# lpf.net
KiCad netlist of a schematic drawn in EAGLE
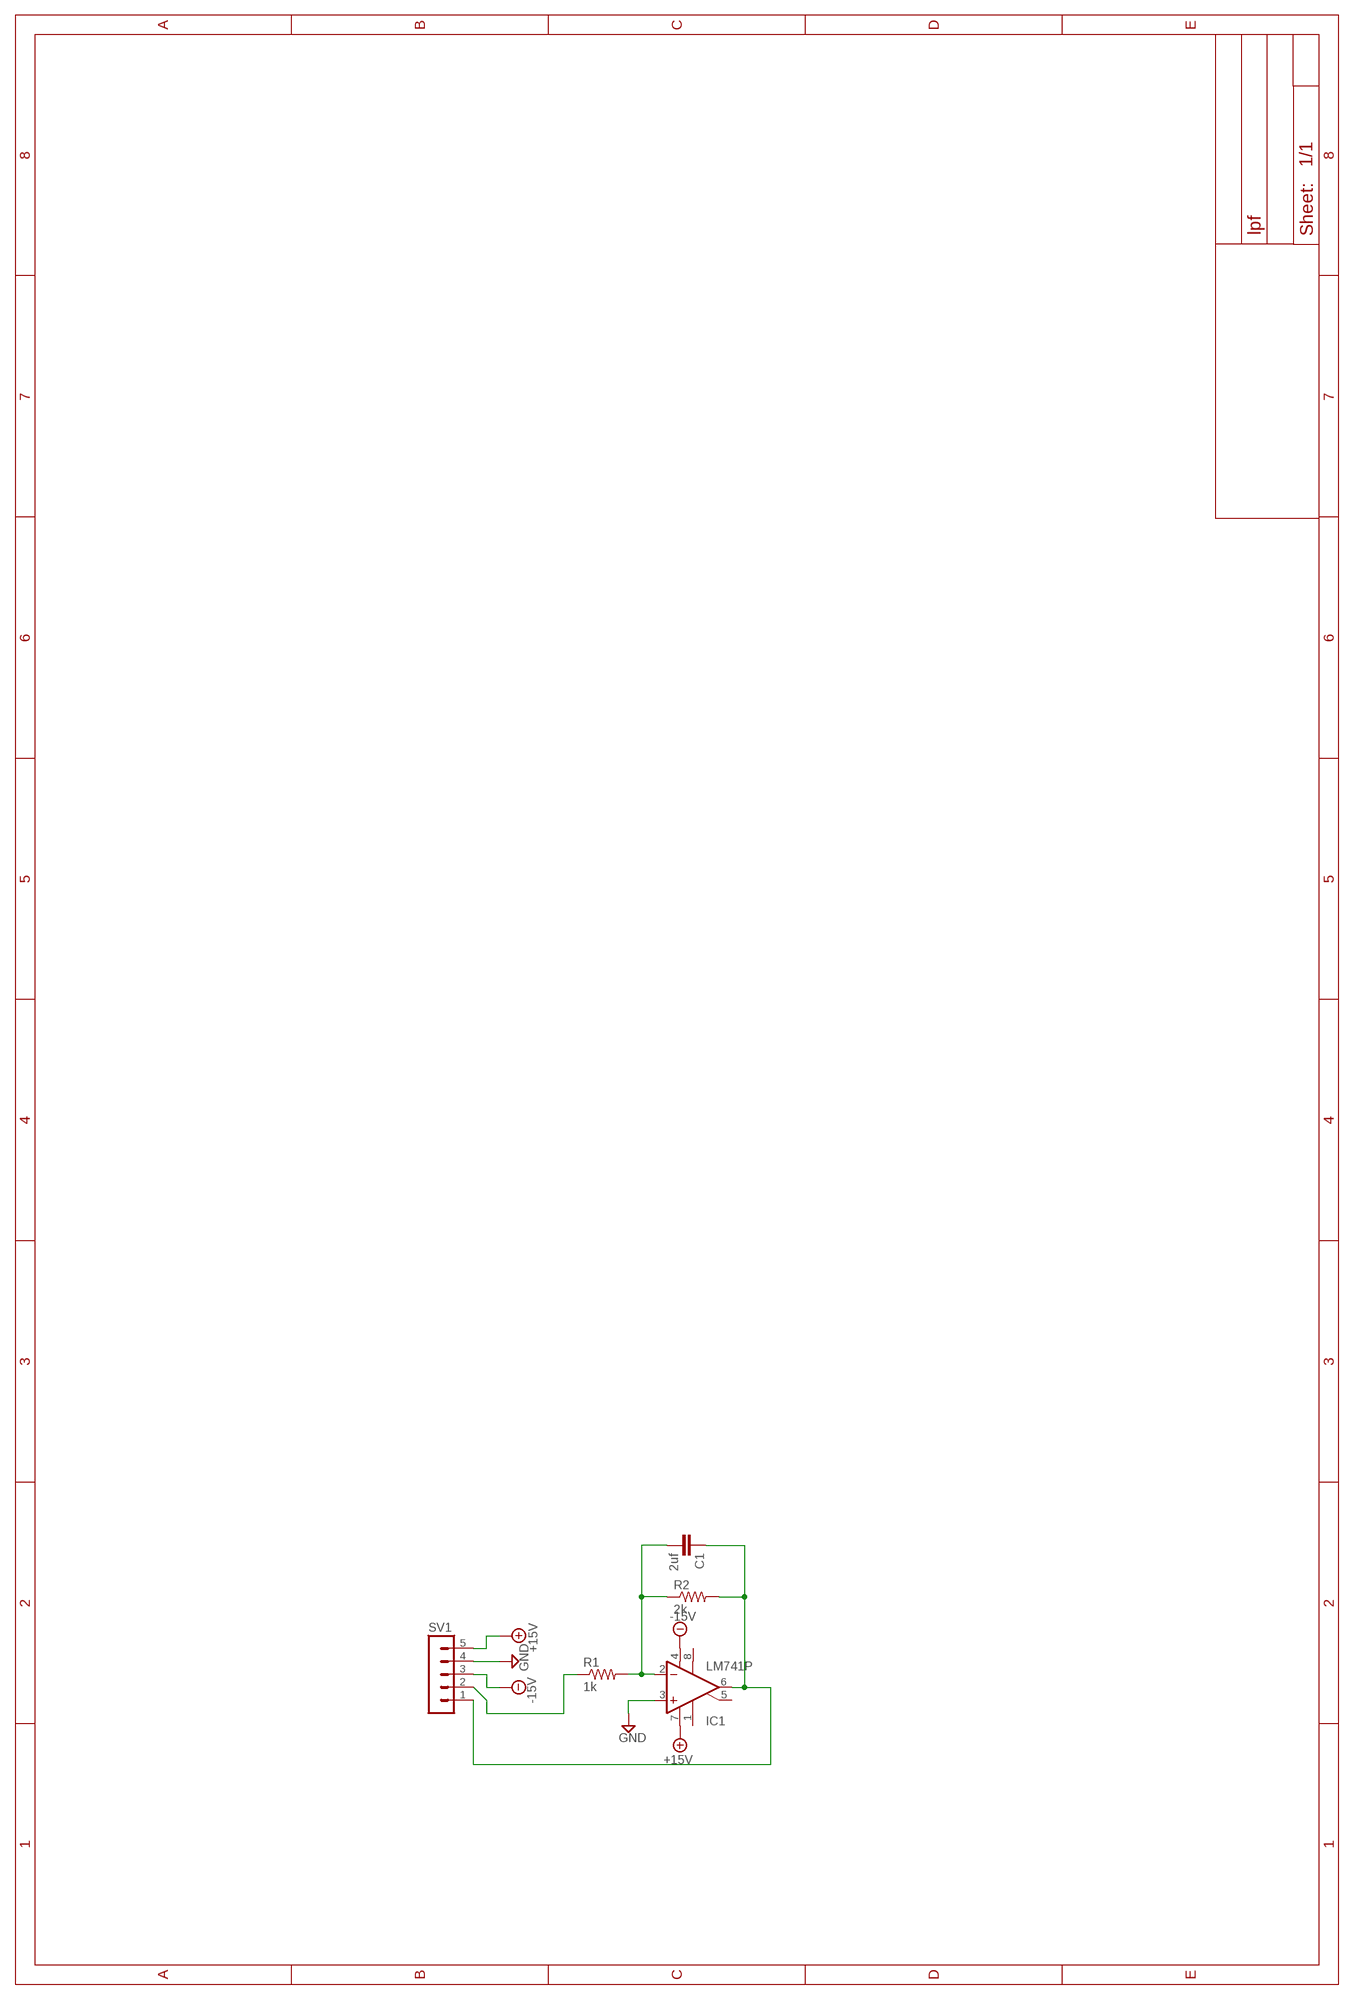
[diagram p0: schematic, sheet 1]

(export (version "E")
  (design (tool "Eeschema 10.0.6"))
  (components
    (comp (ref "C1")
      (value "2uf")
      (footprint "eagle-import:C025-024X044")
      (libsource (lib "eagle-import") (part "C-EU025-024X044"))
    )
    (comp (ref "IC1")
      (value "LM741P")
      (footprint "eagle-import:DIL08")
      (libsource (lib "eagle-import") (part "741PLM"))
    )
    (comp (ref "R1")
      (value "1k")
      (footprint "eagle-import:0204V")
      (libsource (lib "eagle-import") (part "R-US_0204/2V"))
    )
    (comp (ref "R2")
      (value "2k")
      (footprint "eagle-import:0204V")
      (libsource (lib "eagle-import") (part "R-US_0204/2V"))
    )
    (comp (ref "SV1")
      (value "MA05-1")
      (footprint "eagle-import:MA05-1")
      (libsource (lib "eagle-import") (part "MA05-1"))
    )
  )
  (nets
    (net (code "1") (name "+15V") (class "Default")
      (node (ref "IC1") (pin "7") (pinfunction "V+_7") (pintype "power_in"))
      (node (ref "SV1") (pin "5") (pinfunction "5_5") (pintype "passive"))
    )
    (net (code "2") (name "-15V") (class "Default")
      (node (ref "IC1") (pin "4") (pinfunction "V-_4") (pintype "power_in"))
      (node (ref "SV1") (pin "3") (pinfunction "3_3") (pintype "passive"))
    )
    (net (code "3") (name "GND") (class "Default")
      (node (ref "IC1") (pin "3") (pinfunction "+IN_3") (pintype "input"))
      (node (ref "SV1") (pin "4") (pinfunction "4_4") (pintype "passive"))
    )
    (net (code "4") (name "Net-(IC1--IN)") (class "Default")
      (node (ref "C1") (pin "2") (pinfunction "2_2") (pintype "passive"))
      (node (ref "IC1") (pin "2") (pinfunction "-IN_2") (pintype "input"))
      (node (ref "R1") (pin "2") (pinfunction "2_2") (pintype "passive"))
      (node (ref "R2") (pin "1") (pinfunction "1_1") (pintype "passive"))
    )
    (net (code "5") (name "Net-(IC1-OUT)") (class "Default")
      (node (ref "C1") (pin "1") (pinfunction "1_1") (pintype "passive"))
      (node (ref "IC1") (pin "6") (pinfunction "OUT_6") (pintype "output"))
      (node (ref "R2") (pin "2") (pinfunction "2_2") (pintype "passive"))
      (node (ref "SV1") (pin "1") (pinfunction "1_1") (pintype "passive"))
    )
    (net (code "6") (name "Net-(R1-Pad1)") (class "Default")
      (node (ref "R1") (pin "1") (pinfunction "1_1") (pintype "passive"))
      (node (ref "SV1") (pin "2") (pinfunction "2_2") (pintype "passive"))
    )
    (net (code "7") (name "unconnected-(IC1-ON1-Pad1)") (class "Default")
      (node (ref "IC1") (pin "1") (pinfunction "ON1_1") (pintype "passive"))
    )
    (net (code "8") (name "unconnected-(IC1-ON2-Pad5)") (class "Default")
      (node (ref "IC1") (pin "5") (pinfunction "ON2_5") (pintype "passive"))
    )
    (net (code "9") (name "unconnected-(IC1-OPT-Pad8)") (class "Default")
      (node (ref "IC1") (pin "8") (pinfunction "OPT_8") (pintype "passive"))
    )
  )
)
